# schematicEagle.net
KiCad netlist of a schematic drawn in EAGLE
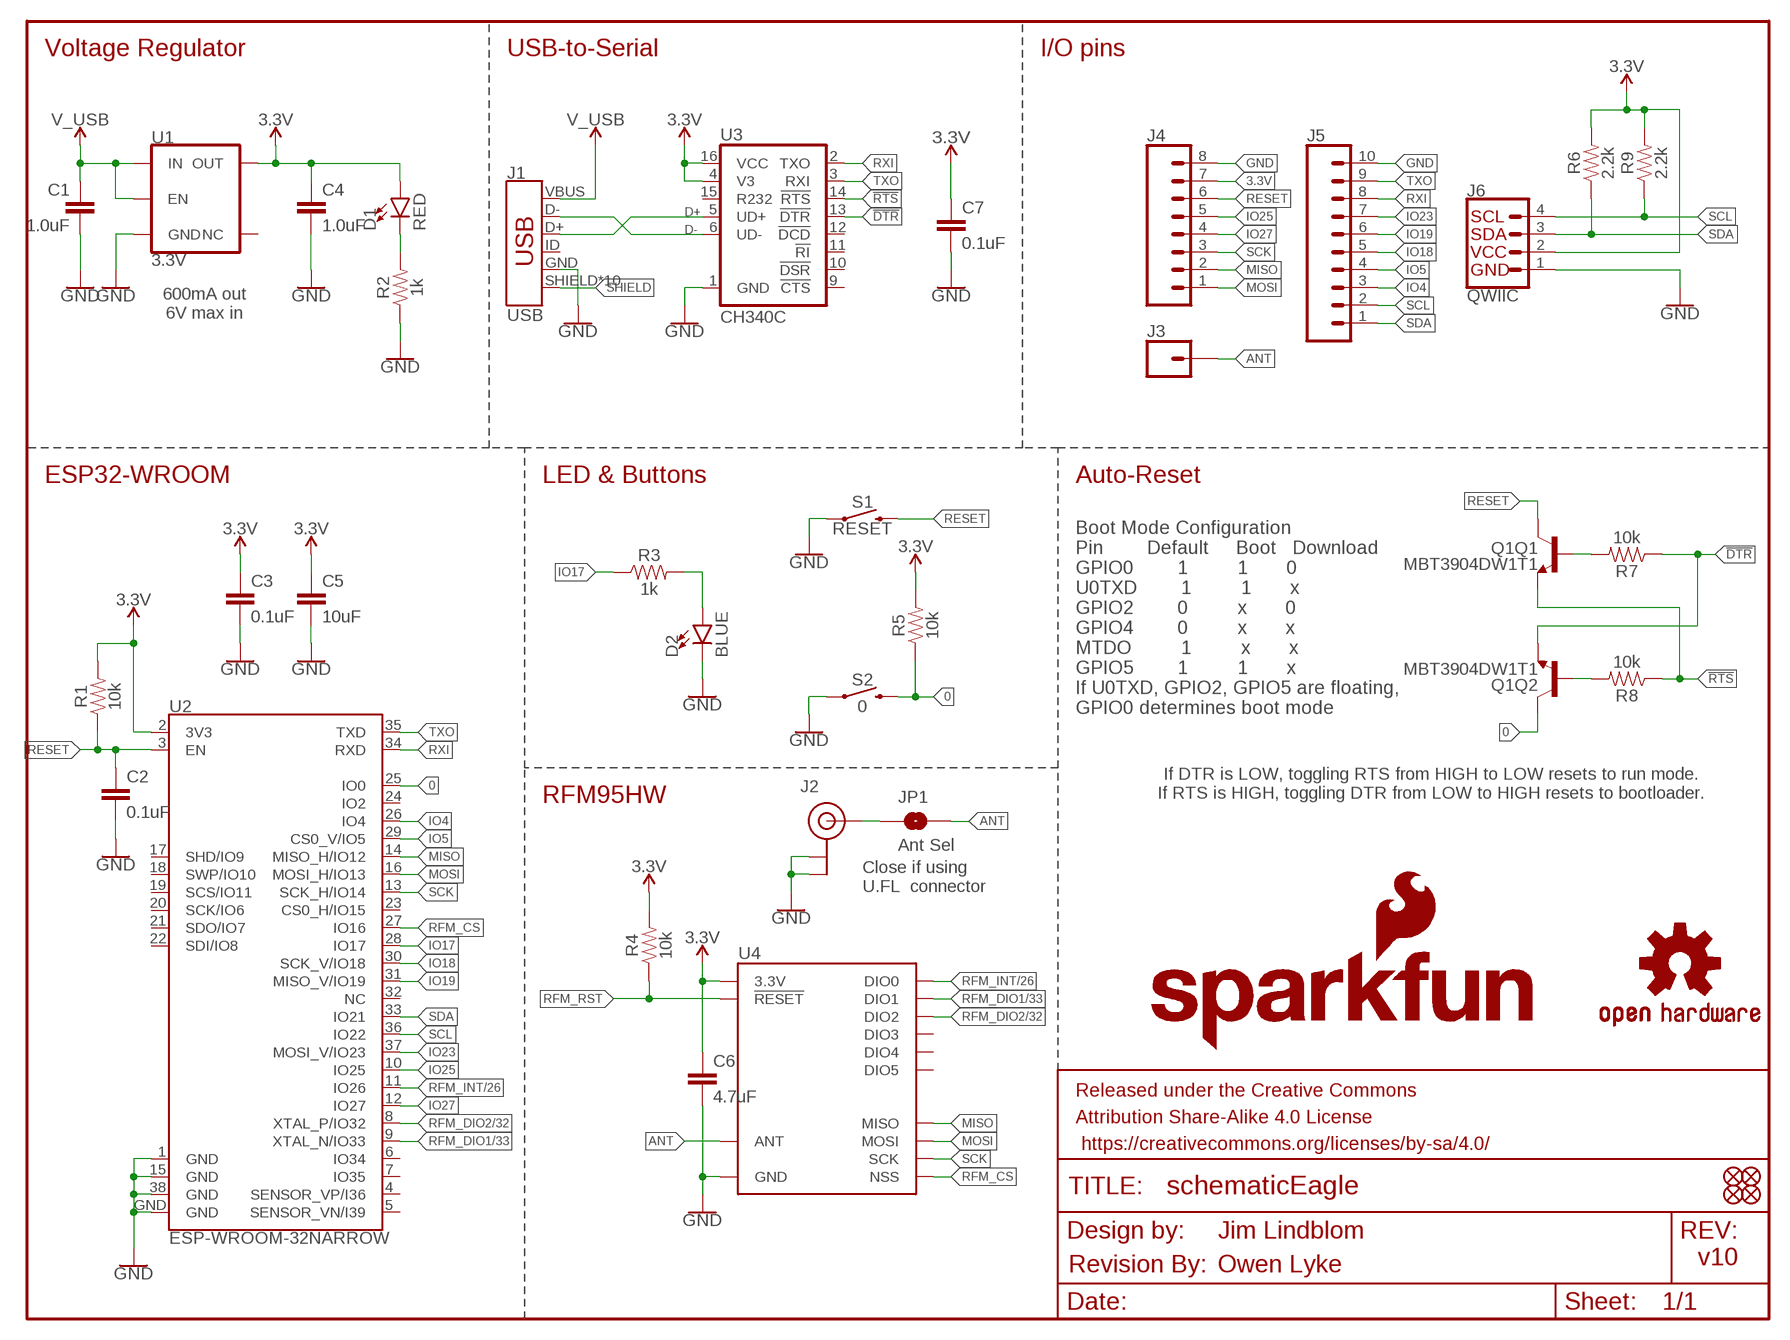
[diagram p0: schematic, sheet 1]

(export (version "E")
  (design (tool "Eeschema 10.0.6"))
  (components
    (comp (ref "C1")
      (value "1.0uF")
      (footprint "eagle-import:0603")
      (libsource (lib "eagle-import") (part "1.0UF-0603-16V-10%"))
    )
    (comp (ref "C2")
      (value "0.1uF")
      (footprint "eagle-import:0603")
      (libsource (lib "eagle-import") (part "0.1UF-0603-25V-(+80/-20%)"))
    )
    (comp (ref "C3")
      (value "0.1uF")
      (footprint "eagle-import:0603")
      (libsource (lib "eagle-import") (part "0.1UF-0603-25V-(+80/-20%)"))
    )
    (comp (ref "C4")
      (value "1.0uF")
      (footprint "eagle-import:0603")
      (libsource (lib "eagle-import") (part "1.0UF-0603-16V-10%"))
    )
    (comp (ref "C5")
      (value "10uF")
      (footprint "eagle-import:0603")
      (libsource (lib "eagle-import") (part "10UF-0603-6.3V-20%"))
    )
    (comp (ref "C6")
      (value "4.7uF")
      (footprint "eagle-import:0603")
      (libsource (lib "eagle-import") (part "4.7UF-0603-6.3V-(10%)"))
    )
    (comp (ref "C7")
      (value "0.1uF")
      (footprint "eagle-import:0603")
      (libsource (lib "eagle-import") (part "0.1UF-0603-25V-5%"))
    )
    (comp (ref "D1")
      (value "RED")
      (footprint "eagle-import:LED-0603")
      (libsource (lib "eagle-import") (part "LED-RED0603"))
    )
    (comp (ref "D2")
      (value "BLUE")
      (footprint "eagle-import:LED-0603")
      (libsource (lib "eagle-import") (part "LED-BLUE0603"))
    )
    (comp (ref "FD1")
      (value "FIDUCIAL1X2")
      (footprint "eagle-import:FIDUCIAL-1X2")
      (libsource (lib "eagle-import") (part "FIDUCIAL1X2"))
    )
    (comp (ref "FD2")
      (value "FIDUCIAL1X2")
      (footprint "eagle-import:FIDUCIAL-1X2")
      (libsource (lib "eagle-import") (part "FIDUCIAL1X2"))
    )
    (comp (ref "FD3")
      (value "FIDUCIAL1X2")
      (footprint "eagle-import:FIDUCIAL-1X2")
      (libsource (lib "eagle-import") (part "FIDUCIAL1X2"))
    )
    (comp (ref "FD4")
      (value "FIDUCIAL1X2")
      (footprint "eagle-import:FIDUCIAL-1X2")
      (libsource (lib "eagle-import") (part "FIDUCIAL1X2"))
    )
    (comp (ref "FRAME1")
      (value "FRAME-LETTER")
      (footprint "eagle-import:CREATIVE_COMMONS")
      (libsource (lib "eagle-import") (part "FRAME-LETTER"))
    )
    (comp (ref "J1")
      (value "USB")
      (footprint "eagle-import:USB-MICROB-PTH-MILL")
      (libsource (lib "eagle-import") (part "USB_MICRO-B_HALF_PTH_MILL"))
    )
    (comp (ref "J2")
      (value "U.FL")
      (footprint "eagle-import:U.FL")
      (libsource (lib "eagle-import") (part "U.FL"))
    )
    (comp (ref "J3")
      (value "CONN_01PTH_NO_SILK_YES_STOP")
      (footprint "eagle-import:1X01_NO_SILK")
      (libsource (lib "eagle-import") (part "CONN_01PTH_NO_SILK_YES_STOP"))
    )
    (comp (ref "J4")
      (value "CONN_08NO_SILK_FEMALE_PTH")
      (footprint "eagle-import:1X08_NO_SILK")
      (libsource (lib "eagle-import") (part "CONN_08NO_SILK_FEMALE_PTH"))
    )
    (comp (ref "J5")
      (value "CONN_10NO_SILK_PTH_FEMALE")
      (footprint "eagle-import:1X10_NO_SILK")
      (libsource (lib "eagle-import") (part "CONN_10NO_SILK_PTH_FEMALE"))
    )
    (comp (ref "J6")
      (value "QWIIC")
      (footprint "eagle-import:1X04_1MM_RA")
      (libsource (lib "eagle-import") (part "QWIIC_CONNECTORJS-1MM"))
    )
    (comp (ref "JP1")
      (value "Ant Sel")
      (footprint "eagle-import:SMT-JUMPER_2_NO_NO-SILK")
      (libsource (lib "eagle-import") (part "JUMPER-SMT_2_NO_NO-SILK"))
    )
    (comp (ref "LOGO1")
      (value "REVISION")
      (footprint "eagle-import:REVISION")
      (libsource (lib "eagle-import") (part "REVISION"))
    )
    (comp (ref "LOGO2")
      (value "SFE_LOGO_NAME_FLAME.1_INCH")
      (footprint "eagle-import:SFE_LOGO_NAME_FLAME_.1")
      (libsource (lib "eagle-import") (part "SFE_LOGO_NAME_FLAME.1_INCH"))
    )
    (comp (ref "LOGO3")
      (value "OSHW-LOGOS")
      (footprint "eagle-import:OSHW-LOGO-S")
      (libsource (lib "eagle-import") (part "OSHW-LOGOS"))
    )
    (comp (ref "Q1")
      (value "MBT3904DW1T1")
      (footprint "eagle-import:SC70-6")
      (libsource (lib "eagle-import") (part "TRANS_NPN_DUAL-MBT3904DW1T1"))
    )
    (comp (ref "R1")
      (value "10k")
      (footprint "eagle-import:0603")
      (libsource (lib "eagle-import") (part "10KOHM-0603-1/10W-1%"))
    )
    (comp (ref "R2")
      (value "1k")
      (footprint "eagle-import:0603")
      (libsource (lib "eagle-import") (part "1KOHM-0603-1/10W-1%"))
    )
    (comp (ref "R3")
      (value "1k")
      (footprint "eagle-import:0603")
      (libsource (lib "eagle-import") (part "1KOHM-0603-1/10W-1%"))
    )
    (comp (ref "R4")
      (value "10k")
      (footprint "eagle-import:0603")
      (libsource (lib "eagle-import") (part "10KOHM-0603-1/10W-1%"))
    )
    (comp (ref "R5")
      (value "10k")
      (footprint "eagle-import:0603")
      (libsource (lib "eagle-import") (part "10KOHM-0603-1/10W-1%"))
    )
    (comp (ref "R6")
      (value "2.2k")
      (footprint "eagle-import:0603")
      (libsource (lib "eagle-import") (part "2.2KOHM-0603-1/10W-1%"))
    )
    (comp (ref "R7")
      (value "10k")
      (footprint "eagle-import:0603")
      (libsource (lib "eagle-import") (part "10KOHM-0603-1/10W-1%"))
    )
    (comp (ref "R8")
      (value "10k")
      (footprint "eagle-import:0603")
      (libsource (lib "eagle-import") (part "10KOHM-0603-1/10W-1%"))
    )
    (comp (ref "R9")
      (value "2.2k")
      (footprint "eagle-import:0603")
      (libsource (lib "eagle-import") (part "2.2KOHM-0603-1/10W-1%"))
    )
    (comp (ref "S1")
      (value "RESET")
      (footprint "eagle-import:TACTILE_SWITCH_SMD_4.6X2.8MM")
      (libsource (lib "eagle-import") (part "MOMENTARY-SWITCH-SPST-SMD-4.6X2.8MM"))
    )
    (comp (ref "S2")
      (value "0")
      (footprint "eagle-import:TACTILE_SWITCH_SMD_4.6X2.8MM")
      (libsource (lib "eagle-import") (part "MOMENTARY-SWITCH-SPST-SMD-4.6X2.8MM"))
    )
    (comp (ref "U1")
      (value "3.3V")
      (footprint "eagle-import:SOT23-5")
      (libsource (lib "eagle-import") (part "V_REG_AP2112K-3.3V"))
    )
    (comp (ref "U2")
      (value "ESP-WROOM-32NARROW")
      (footprint "eagle-import:ESP-WROOM-32-NARROW")
      (libsource (lib "eagle-import") (part "ESP-WROOM-32NARROW"))
    )
    (comp (ref "U3")
      (value "CH340C")
      (footprint "eagle-import:SO016")
      (libsource (lib "eagle-import") (part "CH340C"))
    )
    (comp (ref "U4")
      (value "RFM95W")
      (footprint "eagle-import:RFM95_96_97_98W")
      (libsource (lib "eagle-import") (part "RFM95W"))
    )
  )
  (nets
    (net (code "1") (name "/D+") (class "Default")
      (node (ref "J1") (pin "D+") (pinfunction "D+_D+") (pintype "bidirectional"))
      (node (ref "U3") (pin "5") (pinfunction "UD+_5") (pintype "bidirectional"))
    )
    (net (code "2") (name "/D-") (class "Default")
      (node (ref "J1") (pin "D-") (pinfunction "D-_D-") (pintype "bidirectional"))
      (node (ref "U3") (pin "6") (pinfunction "UD-_6") (pintype "bidirectional"))
    )
    (net (code "3") (name "/~{DTR}") (class "Default")
      (node (ref "Q1") (pin "1") (pinfunction "E_1") (pintype "passive"))
      (node (ref "R7") (pin "1") (pinfunction "1_1") (pintype "passive"))
      (node (ref "U3") (pin "13") (pinfunction "~{DTR}_13") (pintype "bidirectional"))
    )
    (net (code "4") (name "/~{RTS}") (class "Default")
      (node (ref "Q1") (pin "4") (pinfunction "E_4") (pintype "passive"))
      (node (ref "R8") (pin "1") (pinfunction "1_1") (pintype "passive"))
      (node (ref "U3") (pin "14") (pinfunction "~{RTS}_14") (pintype "bidirectional"))
    )
    (net (code "5") (name "0") (class "Default")
      (node (ref "Q1") (pin "6") (pinfunction "C_6") (pintype "passive"))
      (node (ref "R5") (pin "1") (pinfunction "1_1") (pintype "passive"))
      (node (ref "S2") (pin "3") (pinfunction "2_3") (pintype "passive"))
      (node (ref "S2") (pin "4") (pinfunction "2_4") (pintype "passive"))
      (node (ref "U2") (pin "25") (pinfunction "IO0_25") (pintype "bidirectional"))
    )
    (net (code "6") (name "3.3V") (class "Default")
      (node (ref "C3") (pin "1") (pinfunction "1_1") (pintype "passive"))
      (node (ref "C4") (pin "1") (pinfunction "1_1") (pintype "passive"))
      (node (ref "C5") (pin "1") (pinfunction "1_1") (pintype "passive"))
      (node (ref "C6") (pin "1") (pinfunction "1_1") (pintype "passive"))
      (node (ref "C7") (pin "1") (pinfunction "1_1") (pintype "passive"))
      (node (ref "D1") (pin "A") (pinfunction "A_A") (pintype "passive"))
      (node (ref "J4") (pin "7") (pinfunction "7_7") (pintype "passive"))
      (node (ref "J6") (pin "2") (pinfunction "2_2") (pintype "power_in"))
      (node (ref "R1") (pin "2") (pinfunction "2_2") (pintype "passive"))
      (node (ref "R4") (pin "2") (pinfunction "2_2") (pintype "passive"))
      (node (ref "R5") (pin "2") (pinfunction "2_2") (pintype "passive"))
      (node (ref "R6") (pin "2") (pinfunction "2_2") (pintype "passive"))
      (node (ref "R9") (pin "2") (pinfunction "2_2") (pintype "passive"))
      (node (ref "U1") (pin "5") (pinfunction "OUT_5") (pintype "passive"))
      (node (ref "U2") (pin "2") (pinfunction "3V3_2") (pintype "bidirectional"))
      (node (ref "U3") (pin "16") (pinfunction "VCC_16") (pintype "bidirectional"))
      (node (ref "U3") (pin "4") (pinfunction "V3_4") (pintype "bidirectional"))
      (node (ref "U4") (pin "3.3V") (pinfunction "3.3V_3.3V") (pintype "bidirectional"))
    )
    (net (code "7") (name "ANT") (class "Default")
      (node (ref "J3") (pin "1") (pinfunction "1_1") (pintype "passive"))
      (node (ref "JP1") (pin "2") (pinfunction "2_2") (pintype "passive"))
      (node (ref "U4") (pin "ANT") (pinfunction "ANT_ANT") (pintype "bidirectional"))
    )
    (net (code "8") (name "GND") (class "Default")
      (node (ref "C1") (pin "2") (pinfunction "2_2") (pintype "passive"))
      (node (ref "C2") (pin "2") (pinfunction "2_2") (pintype "passive"))
      (node (ref "C3") (pin "2") (pinfunction "2_2") (pintype "passive"))
      (node (ref "C4") (pin "2") (pinfunction "2_2") (pintype "passive"))
      (node (ref "C5") (pin "2") (pinfunction "2_2") (pintype "passive"))
      (node (ref "C6") (pin "2") (pinfunction "2_2") (pintype "passive"))
      (node (ref "C7") (pin "2") (pinfunction "2_2") (pintype "passive"))
      (node (ref "D2") (pin "C") (pinfunction "C_C") (pintype "passive"))
      (node (ref "J1") (pin "GND") (pinfunction "GND_GND") (pintype "power_in"))
      (node (ref "J2") (pin "1") (pinfunction "GND_1") (pintype "bidirectional"))
      (node (ref "J2") (pin "2") (pinfunction "GND_2") (pintype "bidirectional"))
      (node (ref "J4") (pin "8") (pinfunction "8_8") (pintype "passive"))
      (node (ref "J5") (pin "10") (pinfunction "10_10") (pintype "passive"))
      (node (ref "J6") (pin "1") (pinfunction "1_1") (pintype "power_in"))
      (node (ref "R2") (pin "1") (pinfunction "1_1") (pintype "passive"))
      (node (ref "S1") (pin "1") (pinfunction "1_1") (pintype "passive"))
      (node (ref "S1") (pin "2") (pinfunction "1_2") (pintype "passive"))
      (node (ref "S2") (pin "1") (pinfunction "1_1") (pintype "passive"))
      (node (ref "S2") (pin "2") (pinfunction "1_2") (pintype "passive"))
      (node (ref "U1") (pin "2") (pinfunction "GND_2") (pintype "input"))
      (node (ref "U2") (pin "1") (pinfunction "GND_1") (pintype "bidirectional"))
      (node (ref "U2") (pin "15") (pinfunction "GND_15") (pintype "bidirectional"))
      (node (ref "U2") (pin "38") (pinfunction "GND_38") (pintype "bidirectional"))
      (node (ref "U2") (pin "GND") (pinfunction "GND_GND") (pintype "bidirectional"))
      (node (ref "U3") (pin "1") (pinfunction "GND_1") (pintype "bidirectional"))
      (node (ref "U4") (pin "GND@1") (pinfunction "GND_GND@1") (pintype "bidirectional"))
      (node (ref "U4") (pin "GND@2") (pinfunction "GND_GND@2") (pintype "bidirectional"))
      (node (ref "U4") (pin "GND@3") (pinfunction "GND_GND@3") (pintype "bidirectional"))
    )
    (net (code "9") (name "IO4") (class "Default")
      (node (ref "J5") (pin "3") (pinfunction "3_3") (pintype "passive"))
      (node (ref "U2") (pin "26") (pinfunction "IO4_26") (pintype "bidirectional"))
    )
    (net (code "10") (name "IO5") (class "Default")
      (node (ref "J5") (pin "4") (pinfunction "4_4") (pintype "passive"))
      (node (ref "U2") (pin "29") (pinfunction "CS0_V/IO5_29") (pintype "bidirectional"))
    )
    (net (code "11") (name "IO17") (class "Default")
      (node (ref "R3") (pin "1") (pinfunction "1_1") (pintype "passive"))
      (node (ref "U2") (pin "28") (pinfunction "IO17_28") (pintype "bidirectional"))
    )
    (net (code "12") (name "IO18") (class "Default")
      (node (ref "J5") (pin "5") (pinfunction "5_5") (pintype "passive"))
      (node (ref "U2") (pin "30") (pinfunction "SCK_V/IO18_30") (pintype "bidirectional"))
    )
    (net (code "13") (name "IO19") (class "Default")
      (node (ref "J5") (pin "6") (pinfunction "6_6") (pintype "passive"))
      (node (ref "U2") (pin "31") (pinfunction "MISO_V/IO19_31") (pintype "bidirectional"))
    )
    (net (code "14") (name "IO23") (class "Default")
      (node (ref "J5") (pin "7") (pinfunction "7_7") (pintype "passive"))
      (node (ref "U2") (pin "37") (pinfunction "MOSI_V/IO23_37") (pintype "bidirectional"))
    )
    (net (code "15") (name "IO25") (class "Default")
      (node (ref "J4") (pin "5") (pinfunction "5_5") (pintype "passive"))
      (node (ref "U2") (pin "10") (pinfunction "IO25_10") (pintype "bidirectional"))
    )
    (net (code "16") (name "IO27") (class "Default")
      (node (ref "J4") (pin "4") (pinfunction "4_4") (pintype "passive"))
      (node (ref "U2") (pin "12") (pinfunction "IO27_12") (pintype "bidirectional"))
    )
    (net (code "17") (name "MISO") (class "Default")
      (node (ref "J4") (pin "2") (pinfunction "2_2") (pintype "passive"))
      (node (ref "U2") (pin "14") (pinfunction "MISO_H/IO12_14") (pintype "bidirectional"))
      (node (ref "U4") (pin "MISO") (pinfunction "MISO_MISO") (pintype "bidirectional"))
    )
    (net (code "18") (name "MOSI") (class "Default")
      (node (ref "J4") (pin "1") (pinfunction "1_1") (pintype "passive"))
      (node (ref "U2") (pin "16") (pinfunction "MOSI_H/IO13_16") (pintype "bidirectional"))
      (node (ref "U4") (pin "MOSI") (pinfunction "MOSI_MOSI") (pintype "bidirectional"))
    )
    (net (code "19") (name "Net-(D1-PadC)") (class "Default")
      (node (ref "D1") (pin "C") (pinfunction "C_C") (pintype "passive"))
      (node (ref "R2") (pin "2") (pinfunction "2_2") (pintype "passive"))
    )
    (net (code "20") (name "Net-(D2-PadA)") (class "Default")
      (node (ref "D2") (pin "A") (pinfunction "A_A") (pintype "passive"))
      (node (ref "R3") (pin "2") (pinfunction "2_2") (pintype "passive"))
    )
    (net (code "21") (name "Net-(J2-SIGNAL)") (class "Default")
      (node (ref "J2") (pin "FEED") (pinfunction "SIGNAL_FEED") (pintype "bidirectional"))
      (node (ref "JP1") (pin "1") (pinfunction "1_1") (pintype "passive"))
    )
    (net (code "22") (name "Net-(Q1A-B)") (class "Default")
      (node (ref "Q1") (pin "5") (pinfunction "B_5") (pintype "passive"))
      (node (ref "R7") (pin "2") (pinfunction "2_2") (pintype "passive"))
    )
    (net (code "23") (name "Net-(Q1B-B)") (class "Default")
      (node (ref "Q1") (pin "2") (pinfunction "B_2") (pintype "passive"))
      (node (ref "R8") (pin "2") (pinfunction "2_2") (pintype "passive"))
    )
    (net (code "24") (name "RESET") (class "Default")
      (node (ref "C2") (pin "1") (pinfunction "1_1") (pintype "passive"))
      (node (ref "J4") (pin "6") (pinfunction "6_6") (pintype "passive"))
      (node (ref "Q1") (pin "3") (pinfunction "C_3") (pintype "passive"))
      (node (ref "R1") (pin "1") (pinfunction "1_1") (pintype "passive"))
      (node (ref "S1") (pin "3") (pinfunction "2_3") (pintype "passive"))
      (node (ref "S1") (pin "4") (pinfunction "2_4") (pintype "passive"))
      (node (ref "U2") (pin "3") (pinfunction "EN_3") (pintype "bidirectional"))
    )
    (net (code "25") (name "RFM_CS") (class "Default")
      (node (ref "U2") (pin "27") (pinfunction "IO16_27") (pintype "bidirectional"))
      (node (ref "U4") (pin "NSS") (pinfunction "NSS_NSS") (pintype "bidirectional"))
    )
    (net (code "26") (name "RFM_DIO1{slash}33") (class "Default")
      (node (ref "U2") (pin "9") (pinfunction "XTAL_N/IO33_9") (pintype "bidirectional"))
      (node (ref "U4") (pin "DIO1") (pinfunction "DIO1_DIO1") (pintype "bidirectional"))
    )
    (net (code "27") (name "RFM_DIO2{slash}32") (class "Default")
      (node (ref "U2") (pin "8") (pinfunction "XTAL_P/IO32_8") (pintype "bidirectional"))
      (node (ref "U4") (pin "DIO2") (pinfunction "DIO2_DIO2") (pintype "bidirectional"))
    )
    (net (code "28") (name "RFM_INT{slash}26") (class "Default")
      (node (ref "U2") (pin "11") (pinfunction "IO26_11") (pintype "bidirectional"))
      (node (ref "U4") (pin "DIO0") (pinfunction "DIO0_DIO0") (pintype "bidirectional"))
    )
    (net (code "29") (name "RFM_RST") (class "Default")
      (node (ref "R4") (pin "1") (pinfunction "1_1") (pintype "passive"))
      (node (ref "U4") (pin "!RESET") (pinfunction "~{RESET}_!RESET") (pintype "bidirectional"))
    )
    (net (code "30") (name "RXI") (class "Default")
      (node (ref "J5") (pin "8") (pinfunction "8_8") (pintype "passive"))
      (node (ref "U2") (pin "34") (pinfunction "RXD_34") (pintype "bidirectional"))
      (node (ref "U3") (pin "2") (pinfunction "TXO_2") (pintype "bidirectional"))
    )
    (net (code "31") (name "SCK") (class "Default")
      (node (ref "J4") (pin "3") (pinfunction "3_3") (pintype "passive"))
      (node (ref "U2") (pin "13") (pinfunction "SCK_H/IO14_13") (pintype "bidirectional"))
      (node (ref "U4") (pin "SCK") (pinfunction "SCK_SCK") (pintype "bidirectional"))
    )
    (net (code "32") (name "SCL") (class "Default")
      (node (ref "J5") (pin "2") (pinfunction "2_2") (pintype "passive"))
      (node (ref "J6") (pin "4") (pinfunction "4_4") (pintype "passive"))
      (node (ref "R9") (pin "1") (pinfunction "1_1") (pintype "passive"))
      (node (ref "U2") (pin "36") (pinfunction "IO22_36") (pintype "bidirectional"))
    )
    (net (code "33") (name "SDA") (class "Default")
      (node (ref "J5") (pin "1") (pinfunction "1_1") (pintype "passive"))
      (node (ref "J6") (pin "3") (pinfunction "3_3") (pintype "passive"))
      (node (ref "R6") (pin "1") (pinfunction "1_1") (pintype "passive"))
      (node (ref "U2") (pin "33") (pinfunction "IO21_33") (pintype "bidirectional"))
    )
    (net (code "34") (name "SHIELD") (class "Default")
      (node (ref "J1") (pin "SHIELD") (pinfunction "SHIELD_SHIELD") (pintype "bidirectional"))
      (node (ref "J1") (pin "SHIELD10") (pinfunction "SHIELD_SHIELD10") (pintype "bidirectional"))
      (node (ref "J1") (pin "SHIELD2") (pinfunction "SHIELD_SHIELD2") (pintype "bidirectional"))
      (node (ref "J1") (pin "SHIELD3") (pinfunction "SHIELD_SHIELD3") (pintype "bidirectional"))
      (node (ref "J1") (pin "SHIELD4") (pinfunction "SHIELD_SHIELD4") (pintype "bidirectional"))
      (node (ref "J1") (pin "SHIELD5") (pinfunction "SHIELD_SHIELD5") (pintype "bidirectional"))
      (node (ref "J1") (pin "SHIELD6") (pinfunction "SHIELD_SHIELD6") (pintype "bidirectional"))
      (node (ref "J1") (pin "SHIELD7") (pinfunction "SHIELD_SHIELD7") (pintype "bidirectional"))
      (node (ref "J1") (pin "SHIELD8") (pinfunction "SHIELD_SHIELD8") (pintype "bidirectional"))
      (node (ref "J1") (pin "SHIELD9") (pinfunction "SHIELD_SHIELD9") (pintype "bidirectional"))
    )
    (net (code "35") (name "TXO") (class "Default")
      (node (ref "J5") (pin "9") (pinfunction "9_9") (pintype "passive"))
      (node (ref "U2") (pin "35") (pinfunction "TXD_35") (pintype "bidirectional"))
      (node (ref "U3") (pin "3") (pinfunction "RXI_3") (pintype "bidirectional"))
    )
    (net (code "36") (name "V_USB") (class "Default")
      (node (ref "C1") (pin "1") (pinfunction "1_1") (pintype "passive"))
      (node (ref "J1") (pin "VBUS") (pinfunction "VBUS_VBUS") (pintype "power_in"))
      (node (ref "U1") (pin "1") (pinfunction "IN_1") (pintype "input"))
      (node (ref "U1") (pin "3") (pinfunction "EN_3") (pintype "input"))
    )
    (net (code "37") (name "unconnected-(J1-PadID)") (class "Default")
      (node (ref "J1") (pin "ID") (pinfunction "ID_ID") (pintype "bidirectional"))
    )
    (net (code "38") (name "unconnected-(U1-NC-Pad4)") (class "Default")
      (node (ref "U1") (pin "4") (pinfunction "NC_4") (pintype "no_connect"))
    )
    (net (code "39") (name "unconnected-(U2-CS0_H{slash}IO15-Pad23)") (class "Default")
      (node (ref "U2") (pin "23") (pinfunction "CS0_H/IO15_23") (pintype "bidirectional"))
    )
    (net (code "40") (name "unconnected-(U2-IO2-Pad24)") (class "Default")
      (node (ref "U2") (pin "24") (pinfunction "IO2_24") (pintype "bidirectional"))
    )
    (net (code "41") (name "unconnected-(U2-IO34-Pad6)") (class "Default")
      (node (ref "U2") (pin "6") (pinfunction "IO34_6") (pintype "bidirectional"))
    )
    (net (code "42") (name "unconnected-(U2-IO35-Pad7)") (class "Default")
      (node (ref "U2") (pin "7") (pinfunction "IO35_7") (pintype "bidirectional"))
    )
    (net (code "43") (name "unconnected-(U2-NC-Pad32)") (class "Default")
      (node (ref "U2") (pin "32") (pinfunction "NC_32") (pintype "bidirectional"))
    )
    (net (code "44") (name "unconnected-(U2-SCK{slash}IO6-Pad20)") (class "Default")
      (node (ref "U2") (pin "20") (pinfunction "SCK/IO6_20") (pintype "bidirectional"))
    )
    (net (code "45") (name "unconnected-(U2-SCS{slash}IO11-Pad19)") (class "Default")
      (node (ref "U2") (pin "19") (pinfunction "SCS/IO11_19") (pintype "bidirectional"))
    )
    (net (code "46") (name "unconnected-(U2-SDI{slash}IO8-Pad22)") (class "Default")
      (node (ref "U2") (pin "22") (pinfunction "SDI/IO8_22") (pintype "bidirectional"))
    )
    (net (code "47") (name "unconnected-(U2-SDO{slash}IO7-Pad21)") (class "Default")
      (node (ref "U2") (pin "21") (pinfunction "SDO/IO7_21") (pintype "bidirectional"))
    )
    (net (code "48") (name "unconnected-(U2-SENSOR_VN{slash}I39-Pad5)") (class "Default")
      (node (ref "U2") (pin "5") (pinfunction "SENSOR_VN/I39_5") (pintype "bidirectional"))
    )
    (net (code "49") (name "unconnected-(U2-SENSOR_VP{slash}I36-Pad4)") (class "Default")
      (node (ref "U2") (pin "4") (pinfunction "SENSOR_VP/I36_4") (pintype "bidirectional"))
    )
    (net (code "50") (name "unconnected-(U2-SHD{slash}IO9-Pad17)") (class "Default")
      (node (ref "U2") (pin "17") (pinfunction "SHD/IO9_17") (pintype "bidirectional"))
    )
    (net (code "51") (name "unconnected-(U2-SWP{slash}IO10-Pad18)") (class "Default")
      (node (ref "U2") (pin "18") (pinfunction "SWP/IO10_18") (pintype "bidirectional"))
    )
    (net (code "52") (name "unconnected-(U3-R232-Pad15)") (class "Default")
      (node (ref "U3") (pin "15") (pinfunction "R232_15") (pintype "bidirectional"))
    )
    (net (code "53") (name "unconnected-(U3-~{CTS}-Pad9)") (class "Default")
      (node (ref "U3") (pin "9") (pinfunction "~{CTS}_9") (pintype "bidirectional"))
    )
    (net (code "54") (name "unconnected-(U3-~{DCD}-Pad12)") (class "Default")
      (node (ref "U3") (pin "12") (pinfunction "~{DCD}_12") (pintype "bidirectional"))
    )
    (net (code "55") (name "unconnected-(U3-~{DSR}-Pad10)") (class "Default")
      (node (ref "U3") (pin "10") (pinfunction "~{DSR}_10") (pintype "bidirectional"))
    )
    (net (code "56") (name "unconnected-(U3-~{RI}-Pad11)") (class "Default")
      (node (ref "U3") (pin "11") (pinfunction "~{RI}_11") (pintype "bidirectional"))
    )
    (net (code "57") (name "unconnected-(U4-PadDIO3)") (class "Default")
      (node (ref "U4") (pin "DIO3") (pinfunction "DIO3_DIO3") (pintype "bidirectional"))
    )
    (net (code "58") (name "unconnected-(U4-PadDIO4)") (class "Default")
      (node (ref "U4") (pin "DIO4") (pinfunction "DIO4_DIO4") (pintype "bidirectional"))
    )
    (net (code "59") (name "unconnected-(U4-PadDIO5)") (class "Default")
      (node (ref "U4") (pin "DIO5") (pinfunction "DIO5_DIO5") (pintype "bidirectional"))
    )
  )
)
